# LT3652.net
KiCad netlist of a schematic drawn in EAGLE
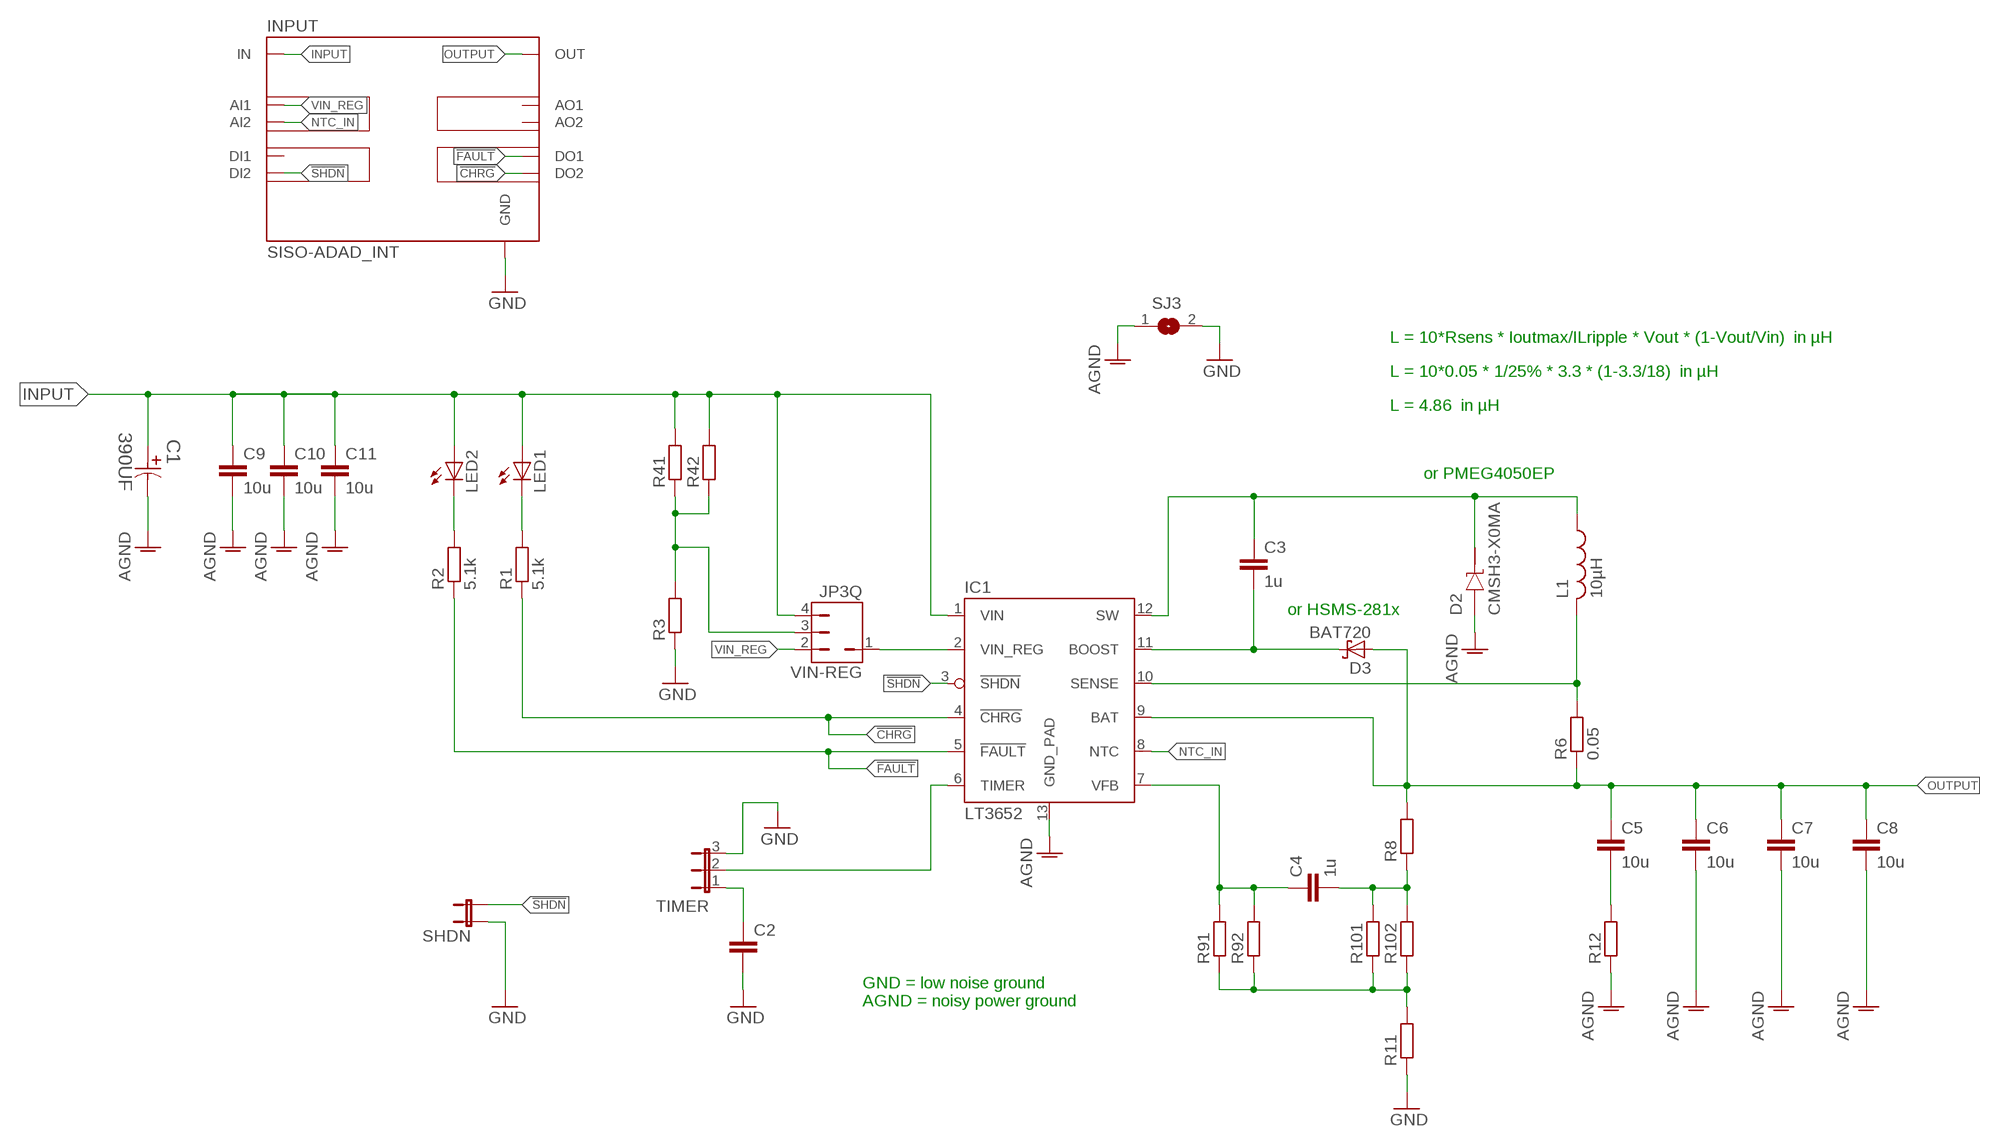
[diagram p0: schematic, sheet 1]

(export (version "E")
  (design (tool "Eeschema 10.0.6"))
  (components
    (comp (ref "C1")
      (value "390UF")
      (footprint "eagle-import:CAPAE1030X1050N")
      (fields (field (name "MPN") "EEE-FPV391UAP") (field (name "TOLERANCE") "±20 %"))
      (libsource (lib "eagle-import") (part "EEE--CASE-GFPV391UAP"))
    )
    (comp (ref "C2")
      (value "C-EUC0805")
      (footprint "eagle-import:C0805")
      (libsource (lib "eagle-import") (part "C-EUC0805"))
    )
    (comp (ref "C3")
      (value "1u")
      (footprint "eagle-import:C0805")
      (libsource (lib "eagle-import") (part "C-EUC0805"))
    )
    (comp (ref "C4")
      (value "1u")
      (footprint "eagle-import:C0805")
      (libsource (lib "eagle-import") (part "C-EUC0805"))
    )
    (comp (ref "C5")
      (value "10u")
      (footprint "eagle-import:C0805")
      (libsource (lib "eagle-import") (part "C-EUC0805"))
    )
    (comp (ref "C6")
      (value "10u")
      (footprint "eagle-import:C0805")
      (libsource (lib "eagle-import") (part "C-EUC0805"))
    )
    (comp (ref "C7")
      (value "10u")
      (footprint "eagle-import:C0805")
      (libsource (lib "eagle-import") (part "C-EUC0805"))
    )
    (comp (ref "C8")
      (value "10u")
      (footprint "eagle-import:C0805")
      (libsource (lib "eagle-import") (part "C-EUC0805"))
    )
    (comp (ref "C9")
      (value "10u")
      (footprint "eagle-import:C0805")
      (libsource (lib "eagle-import") (part "C-EUC0805"))
    )
    (comp (ref "C10")
      (value "10u")
      (footprint "eagle-import:C0805")
      (libsource (lib "eagle-import") (part "C-EUC0805"))
    )
    (comp (ref "C11")
      (value "10u")
      (footprint "eagle-import:C0805")
      (libsource (lib "eagle-import") (part "C-EUC0805"))
    )
    (comp (ref "D2")
      (value "CMSH3-X0MA")
      (footprint "eagle-import:DIODE_SMA")
      (libsource (lib "eagle-import") (part "CMSH3-X0MA"))
    )
    (comp (ref "D3")
      (value "BAT720")
      (footprint "eagle-import:SOT23")
      (libsource (lib "eagle-import") (part "BAS70"))
    )
    (comp (ref "IC1")
      (value "LT3652")
      (footprint "eagle-import:MSOP-12_GND")
      (libsource (lib "eagle-import") (part "LT3652"))
    )
    (comp (ref "INPUT")
      (value "SISO-ADAD_INT")
      (footprint "eagle-import:SISO-ADAD")
      (libsource (lib "eagle-import") (part "SISO-ADAD_INT"))
    )
    (comp (ref "L1")
      (value "10µH")
      (footprint "eagle-import:2525")
      (libsource (lib "eagle-import") (part "IHLP-2525CZ-01"))
    )
    (comp (ref "LED1")
      (value "LEDCHIP-LED0805")
      (footprint "eagle-import:CHIP-LED0805")
      (libsource (lib "eagle-import") (part "LEDCHIP-LED0805"))
    )
    (comp (ref "LED2")
      (value "LEDCHIP-LED0805")
      (footprint "eagle-import:CHIP-LED0805")
      (libsource (lib "eagle-import") (part "LEDCHIP-LED0805"))
    )
    (comp (ref "R1")
      (value "5.1k")
      (footprint "eagle-import:R0805")
      (libsource (lib "eagle-import") (part "R-EU_R0805"))
    )
    (comp (ref "R2")
      (value "5.1k")
      (footprint "eagle-import:R0805")
      (libsource (lib "eagle-import") (part "R-EU_R0805"))
    )
    (comp (ref "R3")
      (value "R-EU_R0805")
      (footprint "eagle-import:R0805")
      (libsource (lib "eagle-import") (part "R-EU_R0805"))
    )
    (comp (ref "R6")
      (value "0.05")
      (footprint "eagle-import:R1206")
      (libsource (lib "eagle-import") (part "R-EU_R1206"))
    )
    (comp (ref "R8")
      (value "R-EU_R0805")
      (footprint "eagle-import:R0805")
      (libsource (lib "eagle-import") (part "R-EU_R0805"))
    )
    (comp (ref "R11")
      (value "R-EU_R0805")
      (footprint "eagle-import:R0805")
      (libsource (lib "eagle-import") (part "R-EU_R0805"))
    )
    (comp (ref "R12")
      (value "R-EU_R0805")
      (footprint "eagle-import:R0805")
      (libsource (lib "eagle-import") (part "R-EU_R0805"))
    )
    (comp (ref "R41")
      (value "R-EU_R0805")
      (footprint "eagle-import:R0805")
      (libsource (lib "eagle-import") (part "R-EU_R0805"))
    )
    (comp (ref "R42")
      (value "R-EU_R0805")
      (footprint "eagle-import:R0805")
      (libsource (lib "eagle-import") (part "R-EU_R0805"))
    )
    (comp (ref "R91")
      (value "R-EU_R0805")
      (footprint "eagle-import:R0805")
      (libsource (lib "eagle-import") (part "R-EU_R0805"))
    )
    (comp (ref "R92")
      (value "R-EU_R0805")
      (footprint "eagle-import:R0805")
      (libsource (lib "eagle-import") (part "R-EU_R0805"))
    )
    (comp (ref "R101")
      (value "R-EU_R0805")
      (footprint "eagle-import:R0805")
      (libsource (lib "eagle-import") (part "R-EU_R0805"))
    )
    (comp (ref "R102")
      (value "R-EU_R0805")
      (footprint "eagle-import:R0805")
      (libsource (lib "eagle-import") (part "R-EU_R0805"))
    )
    (comp (ref "SHDN")
      (value "JP2_SMALL_PAD")
      (footprint "eagle-import:JP2_SMALL_PAD")
      (libsource (lib "eagle-import") (part "JP2_SMALL_PAD"))
    )
    (comp (ref "SJ3")
      (value "SJ2")
      (footprint "eagle-import:SJ2")
      (libsource (lib "eagle-import") (part "SJ2"))
    )
    (comp (ref "TIMER")
      (value "JP3_SMALL_PAD")
      (footprint "eagle-import:JP3_SMALL_PAD")
      (libsource (lib "eagle-import") (part "JP3_SMALL_PAD"))
    )
    (comp (ref "VIN-REG")
      (value "JP3Q")
      (footprint "eagle-import:JP1-3")
      (libsource (lib "eagle-import") (part "JP3Q"))
    )
  )
  (nets
    (net (code "1") (name "/~{CHRG}") (class "Default")
      (node (ref "IC1") (pin "4") (pinfunction "~{CHRG}_4") (pintype "bidirectional"))
      (node (ref "INPUT") (pin "DO2") (pinfunction "DO2_DO2") (pintype "input"))
      (node (ref "R1") (pin "1") (pinfunction "1_1") (pintype "passive"))
    )
    (net (code "2") (name "/~{FAULT}") (class "Default")
      (node (ref "IC1") (pin "5") (pinfunction "~{FAULT}_5") (pintype "bidirectional"))
      (node (ref "INPUT") (pin "DO1") (pinfunction "DO1_DO1") (pintype "input"))
      (node (ref "R2") (pin "1") (pinfunction "1_1") (pintype "passive"))
    )
    (net (code "3") (name "/~{SHDN}") (class "Default")
      (node (ref "IC1") (pin "3") (pinfunction "~{SHDN}_3") (pintype "bidirectional"))
      (node (ref "INPUT") (pin "DI2") (pinfunction "DI2_DI2") (pintype "output"))
      (node (ref "SHDN") (pin "2") (pinfunction "2_2") (pintype "passive"))
    )
    (net (code "4") (name "AGND") (class "Default")
      (node (ref "C1") (pin "2") (pinfunction "2_2") (pintype "passive"))
      (node (ref "C10") (pin "2") (pinfunction "2_2") (pintype "passive"))
      (node (ref "C11") (pin "2") (pinfunction "2_2") (pintype "passive"))
      (node (ref "C6") (pin "2") (pinfunction "2_2") (pintype "passive"))
      (node (ref "C7") (pin "2") (pinfunction "2_2") (pintype "passive"))
      (node (ref "C8") (pin "2") (pinfunction "2_2") (pintype "passive"))
      (node (ref "C9") (pin "2") (pinfunction "2_2") (pintype "passive"))
      (node (ref "D2") (pin "A") (pinfunction "A_A") (pintype "bidirectional"))
      (node (ref "IC1") (pin "13") (pinfunction "GND_PAD_13") (pintype "bidirectional"))
      (node (ref "R12") (pin "1") (pinfunction "1_1") (pintype "passive"))
      (node (ref "SJ3") (pin "1") (pinfunction "1_1") (pintype "passive"))
    )
    (net (code "5") (name "GND") (class "Default")
      (node (ref "C2") (pin "2") (pinfunction "2_2") (pintype "passive"))
      (node (ref "INPUT") (pin "GND1") (pinfunction "GND_GND1") (pintype "power_in"))
      (node (ref "INPUT") (pin "GND2") (pinfunction "GND_GND2") (pintype "power_in"))
      (node (ref "INPUT") (pin "GND3") (pinfunction "GND_GND3") (pintype "power_in"))
      (node (ref "INPUT") (pin "GND4") (pinfunction "GND_GND4") (pintype "power_in"))
      (node (ref "R11") (pin "1") (pinfunction "1_1") (pintype "passive"))
      (node (ref "R3") (pin "1") (pinfunction "1_1") (pintype "passive"))
      (node (ref "SHDN") (pin "1") (pinfunction "1_1") (pintype "passive"))
      (node (ref "SJ3") (pin "2") (pinfunction "2_2") (pintype "passive"))
      (node (ref "TIMER") (pin "3") (pinfunction "3_3") (pintype "passive"))
    )
    (net (code "6") (name "INPUT") (class "Default")
      (node (ref "C1") (pin "1") (pinfunction "1_1") (pintype "passive"))
      (node (ref "C10") (pin "1") (pinfunction "1_1") (pintype "passive"))
      (node (ref "C11") (pin "1") (pinfunction "1_1") (pintype "passive"))
      (node (ref "C9") (pin "1") (pinfunction "1_1") (pintype "passive"))
      (node (ref "IC1") (pin "1") (pinfunction "VIN_1") (pintype "bidirectional"))
      (node (ref "INPUT") (pin "IN1") (pinfunction "IN_IN1") (pintype "output"))
      (node (ref "INPUT") (pin "IN2") (pinfunction "IN_IN2") (pintype "output"))
      (node (ref "INPUT") (pin "IN3") (pinfunction "IN_IN3") (pintype "output"))
      (node (ref "INPUT") (pin "IN4") (pinfunction "IN_IN4") (pintype "output"))
      (node (ref "LED1") (pin "A") (pinfunction "A_A") (pintype "passive"))
      (node (ref "LED2") (pin "A") (pinfunction "A_A") (pintype "passive"))
      (node (ref "R41") (pin "2") (pinfunction "2_2") (pintype "passive"))
      (node (ref "R42") (pin "2") (pinfunction "2_2") (pintype "passive"))
      (node (ref "VIN-REG") (pin "4") (pinfunction "4_4") (pintype "passive"))
    )
    (net (code "7") (name "NTC_IN") (class "Default")
      (node (ref "IC1") (pin "8") (pinfunction "NTC_8") (pintype "bidirectional"))
      (node (ref "INPUT") (pin "AI2") (pinfunction "AI2_AI2") (pintype "output"))
    )
    (net (code "8") (name "Net-(C2-Pad1)") (class "Default")
      (node (ref "C2") (pin "1") (pinfunction "1_1") (pintype "passive"))
      (node (ref "TIMER") (pin "1") (pinfunction "1_1") (pintype "passive"))
    )
    (net (code "9") (name "Net-(C4-Pad2)") (class "Default")
      (node (ref "C4") (pin "2") (pinfunction "2_2") (pintype "passive"))
      (node (ref "R101") (pin "2") (pinfunction "2_2") (pintype "passive"))
      (node (ref "R102") (pin "2") (pinfunction "2_2") (pintype "passive"))
      (node (ref "R8") (pin "1") (pinfunction "1_1") (pintype "passive"))
    )
    (net (code "10") (name "Net-(C5-Pad2)") (class "Default")
      (node (ref "C5") (pin "2") (pinfunction "2_2") (pintype "passive"))
      (node (ref "R12") (pin "2") (pinfunction "2_2") (pintype "passive"))
    )
    (net (code "11") (name "Net-(D3-C)") (class "Default")
      (node (ref "C3") (pin "2") (pinfunction "2_2") (pintype "passive"))
      (node (ref "D3") (pin "3") (pinfunction "C_3") (pintype "passive"))
      (node (ref "IC1") (pin "11") (pinfunction "BOOST_11") (pintype "bidirectional"))
    )
    (net (code "12") (name "Net-(IC1-SENSE)") (class "Default")
      (node (ref "IC1") (pin "10") (pinfunction "SENSE_10") (pintype "bidirectional"))
      (node (ref "L1") (pin "P$1") (pinfunction "P$1_P$1") (pintype "passive"))
      (node (ref "R6") (pin "2") (pinfunction "2_2") (pintype "passive"))
    )
    (net (code "13") (name "Net-(IC1-SW)") (class "Default")
      (node (ref "C3") (pin "1") (pinfunction "1_1") (pintype "passive"))
      (node (ref "D2") (pin "C") (pinfunction "C_C") (pintype "bidirectional"))
      (node (ref "IC1") (pin "12") (pinfunction "SW_12") (pintype "bidirectional"))
      (node (ref "L1") (pin "P$2") (pinfunction "P$2_P$2") (pintype "passive"))
    )
    (net (code "14") (name "Net-(IC1-TIMER)") (class "Default")
      (node (ref "IC1") (pin "6") (pinfunction "TIMER_6") (pintype "bidirectional"))
      (node (ref "TIMER") (pin "2") (pinfunction "2_2") (pintype "passive"))
    )
    (net (code "15") (name "Net-(IC1-VFB)") (class "Default")
      (node (ref "C4") (pin "1") (pinfunction "1_1") (pintype "passive"))
      (node (ref "IC1") (pin "7") (pinfunction "VFB_7") (pintype "bidirectional"))
      (node (ref "R91") (pin "2") (pinfunction "2_2") (pintype "passive"))
      (node (ref "R92") (pin "2") (pinfunction "2_2") (pintype "passive"))
    )
    (net (code "16") (name "Net-(IC1-VIN_REG)") (class "Default")
      (node (ref "IC1") (pin "2") (pinfunction "VIN_REG_2") (pintype "bidirectional"))
      (node (ref "VIN-REG") (pin "1") (pinfunction "1_1") (pintype "passive"))
    )
    (net (code "17") (name "Net-(LED1-PadC)") (class "Default")
      (node (ref "LED1") (pin "C") (pinfunction "C_C") (pintype "passive"))
      (node (ref "R1") (pin "2") (pinfunction "2_2") (pintype "passive"))
    )
    (net (code "18") (name "Net-(LED2-PadC)") (class "Default")
      (node (ref "LED2") (pin "C") (pinfunction "C_C") (pintype "passive"))
      (node (ref "R2") (pin "2") (pinfunction "2_2") (pintype "passive"))
    )
    (net (code "19") (name "Net-(R3-Pad2)") (class "Default")
      (node (ref "R3") (pin "2") (pinfunction "2_2") (pintype "passive"))
      (node (ref "R41") (pin "1") (pinfunction "1_1") (pintype "passive"))
      (node (ref "R42") (pin "1") (pinfunction "1_1") (pintype "passive"))
      (node (ref "VIN-REG") (pin "3") (pinfunction "3_3") (pintype "passive"))
    )
    (net (code "20") (name "Net-(R101-Pad1)") (class "Default")
      (node (ref "R101") (pin "1") (pinfunction "1_1") (pintype "passive"))
      (node (ref "R102") (pin "1") (pinfunction "1_1") (pintype "passive"))
      (node (ref "R11") (pin "2") (pinfunction "2_2") (pintype "passive"))
      (node (ref "R91") (pin "1") (pinfunction "1_1") (pintype "passive"))
      (node (ref "R92") (pin "1") (pinfunction "1_1") (pintype "passive"))
    )
    (net (code "21") (name "OUTPUT") (class "Default")
      (node (ref "C5") (pin "1") (pinfunction "1_1") (pintype "passive"))
      (node (ref "C6") (pin "1") (pinfunction "1_1") (pintype "passive"))
      (node (ref "C7") (pin "1") (pinfunction "1_1") (pintype "passive"))
      (node (ref "C8") (pin "1") (pinfunction "1_1") (pintype "passive"))
      (node (ref "D3") (pin "1") (pinfunction "A_1") (pintype "passive"))
      (node (ref "IC1") (pin "9") (pinfunction "BAT_9") (pintype "bidirectional"))
      (node (ref "INPUT") (pin "OUT1_1") (pinfunction "OUT_OUT1_1") (pintype "input"))
      (node (ref "INPUT") (pin "OUT1_2") (pinfunction "OUT_OUT1_2") (pintype "input"))
      (node (ref "INPUT") (pin "OUT1_3") (pinfunction "OUT_OUT1_3") (pintype "input"))
      (node (ref "INPUT") (pin "OUT1_4") (pinfunction "OUT_OUT1_4") (pintype "input"))
      (node (ref "R6") (pin "1") (pinfunction "1_1") (pintype "passive"))
      (node (ref "R8") (pin "2") (pinfunction "2_2") (pintype "passive"))
    )
    (net (code "22") (name "VIN_REG") (class "Default")
      (node (ref "INPUT") (pin "AI1") (pinfunction "AI1_AI1") (pintype "output"))
      (node (ref "VIN-REG") (pin "2") (pinfunction "2_2") (pintype "passive"))
    )
    (net (code "23") (name "unconnected-(INPUT-PadAO1)") (class "Default")
      (node (ref "INPUT") (pin "AO1") (pinfunction "AO1_AO1") (pintype "input"))
    )
    (net (code "24") (name "unconnected-(INPUT-PadAO2)") (class "Default")
      (node (ref "INPUT") (pin "AO2") (pinfunction "AO2_AO2") (pintype "input"))
    )
    (net (code "25") (name "unconnected-(INPUT-PadDI1)") (class "Default")
      (node (ref "INPUT") (pin "DI1") (pinfunction "DI1_DI1") (pintype "output"))
    )
  )
)
